# YOTSUBA__X_EM_ver_2_0.net
KiCad netlist of a schematic drawn in EAGLE
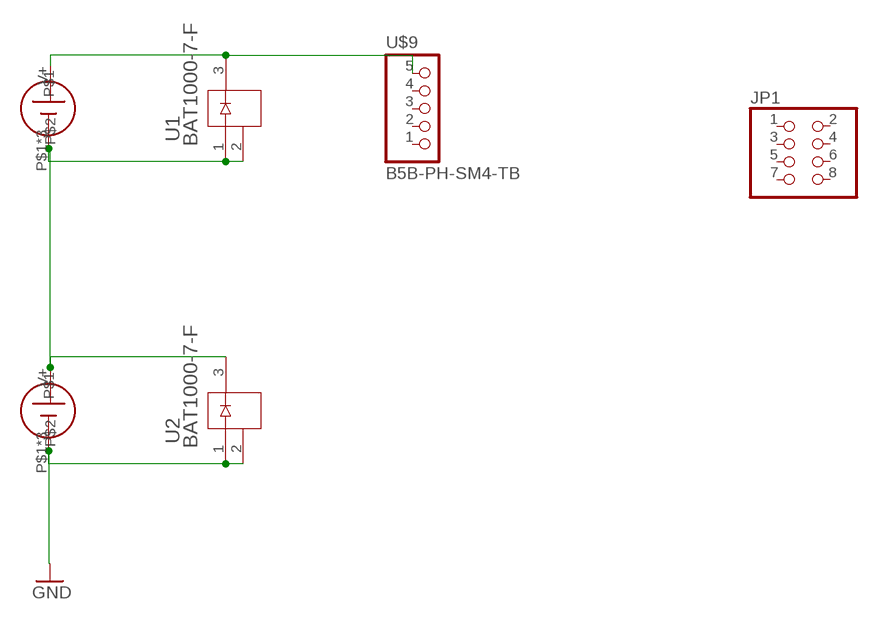
[diagram p0: schematic, sheet 1]

(export (version "E")
  (design (tool "Eeschema 10.0.6"))
  (components
    (comp (ref "JP1")
      (value "PINHD-2X4")
      (footprint "eagle-import:2X04")
      (libsource (lib "eagle-import") (part "PINHD-2X4"))
    )
    (comp (ref "U$1")
      (value "SOLAR_2.0_SOLAR")
      (footprint "eagle-import:SOLAR_2.0_SOLAR")
      (libsource (lib "eagle-import") (part "SOLAR_2.0_SOLAR"))
    )
    (comp (ref "U$8")
      (value "SOLAR_2.0_SOLAR")
      (footprint "eagle-import:SOLAR_2.0_SOLAR")
      (libsource (lib "eagle-import") (part "SOLAR_2.0_SOLAR"))
    )
    (comp (ref "U$9")
      (value "B5B-PH-SM4-TB")
      (footprint "eagle-import:B5B-PH-SM4-TB")
      (libsource (lib "eagle-import") (part "B5B-PH-SM4-TB"))
    )
    (comp (ref "U1")
      (value "BAT1000-7-F")
      (footprint "eagle-import:SOT23_BAT_DIO")
      (fields (field (name "COPYRIGHT") "Copyright (C) 2022 Ultra Librarian. All rights reserved."))
      (libsource (lib "eagle-import") (part "BAT1000-7-F"))
    )
    (comp (ref "U2")
      (value "BAT1000-7-F")
      (footprint "eagle-import:SOT23_BAT_DIO")
      (fields (field (name "COPYRIGHT") "Copyright (C) 2022 Ultra Librarian. All rights reserved."))
      (libsource (lib "eagle-import") (part "BAT1000-7-F"))
    )
  )
  (nets
    (net (code "1") (name "GND") (class "Default")
      (node (ref "U$8") (pin "P$1") (pinfunction "P$1_P$1") (pintype "bidirectional"))
      (node (ref "U$8") (pin "P$2") (pinfunction "P$1_P$2") (pintype "bidirectional"))
      (node (ref "U$8") (pin "P$3") (pinfunction "P$1_P$3") (pintype "bidirectional"))
      (node (ref "U2") (pin "1") (pinfunction "1_1") (pintype "passive"))
      (node (ref "U2") (pin "2") (pinfunction "2_2") (pintype "passive"))
    )
    (net (code "2") (name "Net-(U$1-P$2)") (class "Default")
      (node (ref "U$1") (pin "V+") (pinfunction "P$2_V+") (pintype "bidirectional"))
      (node (ref "U$9") (pin "5") (pinfunction "5_5") (pintype "passive"))
      (node (ref "U1") (pin "3") (pinfunction "3_3") (pintype "passive"))
    )
    (net (code "3") (name "Net-(U$8-P$2)") (class "Default")
      (node (ref "U$1") (pin "P$1") (pinfunction "P$1_P$1") (pintype "bidirectional"))
      (node (ref "U$1") (pin "P$2") (pinfunction "P$1_P$2") (pintype "bidirectional"))
      (node (ref "U$1") (pin "P$3") (pinfunction "P$1_P$3") (pintype "bidirectional"))
      (node (ref "U$8") (pin "V+") (pinfunction "P$2_V+") (pintype "bidirectional"))
      (node (ref "U1") (pin "1") (pinfunction "1_1") (pintype "passive"))
      (node (ref "U1") (pin "2") (pinfunction "2_2") (pintype "passive"))
      (node (ref "U2") (pin "3") (pinfunction "3_3") (pintype "passive"))
    )
    (net (code "4") (name "unconnected-(JP1-Pad1)") (class "Default")
      (node (ref "JP1") (pin "1") (pinfunction "1_1") (pintype "passive"))
    )
    (net (code "5") (name "unconnected-(JP1-Pad2)") (class "Default")
      (node (ref "JP1") (pin "2") (pinfunction "2_2") (pintype "passive"))
    )
    (net (code "6") (name "unconnected-(JP1-Pad3)") (class "Default")
      (node (ref "JP1") (pin "3") (pinfunction "3_3") (pintype "passive"))
    )
    (net (code "7") (name "unconnected-(JP1-Pad4)") (class "Default")
      (node (ref "JP1") (pin "4") (pinfunction "4_4") (pintype "passive"))
    )
    (net (code "8") (name "unconnected-(JP1-Pad5)") (class "Default")
      (node (ref "JP1") (pin "5") (pinfunction "5_5") (pintype "passive"))
    )
    (net (code "9") (name "unconnected-(JP1-Pad6)") (class "Default")
      (node (ref "JP1") (pin "6") (pinfunction "6_6") (pintype "passive"))
    )
    (net (code "10") (name "unconnected-(JP1-Pad7)") (class "Default")
      (node (ref "JP1") (pin "7") (pinfunction "7_7") (pintype "passive"))
    )
    (net (code "11") (name "unconnected-(JP1-Pad8)") (class "Default")
      (node (ref "JP1") (pin "8") (pinfunction "8_8") (pintype "passive"))
    )
    (net (code "12") (name "unconnected-(U$9-Pad1)") (class "Default")
      (node (ref "U$9") (pin "1") (pinfunction "1_1") (pintype "passive"))
    )
    (net (code "13") (name "unconnected-(U$9-Pad2)") (class "Default")
      (node (ref "U$9") (pin "2") (pinfunction "2_2") (pintype "passive"))
    )
    (net (code "14") (name "unconnected-(U$9-Pad3)") (class "Default")
      (node (ref "U$9") (pin "3") (pinfunction "3_3") (pintype "passive"))
    )
    (net (code "15") (name "unconnected-(U$9-Pad4)") (class "Default")
      (node (ref "U$9") (pin "4") (pinfunction "4_4") (pintype "passive"))
    )
  )
)
